# 03-Display.net
KiCad netlist of a schematic drawn in Altium Designer
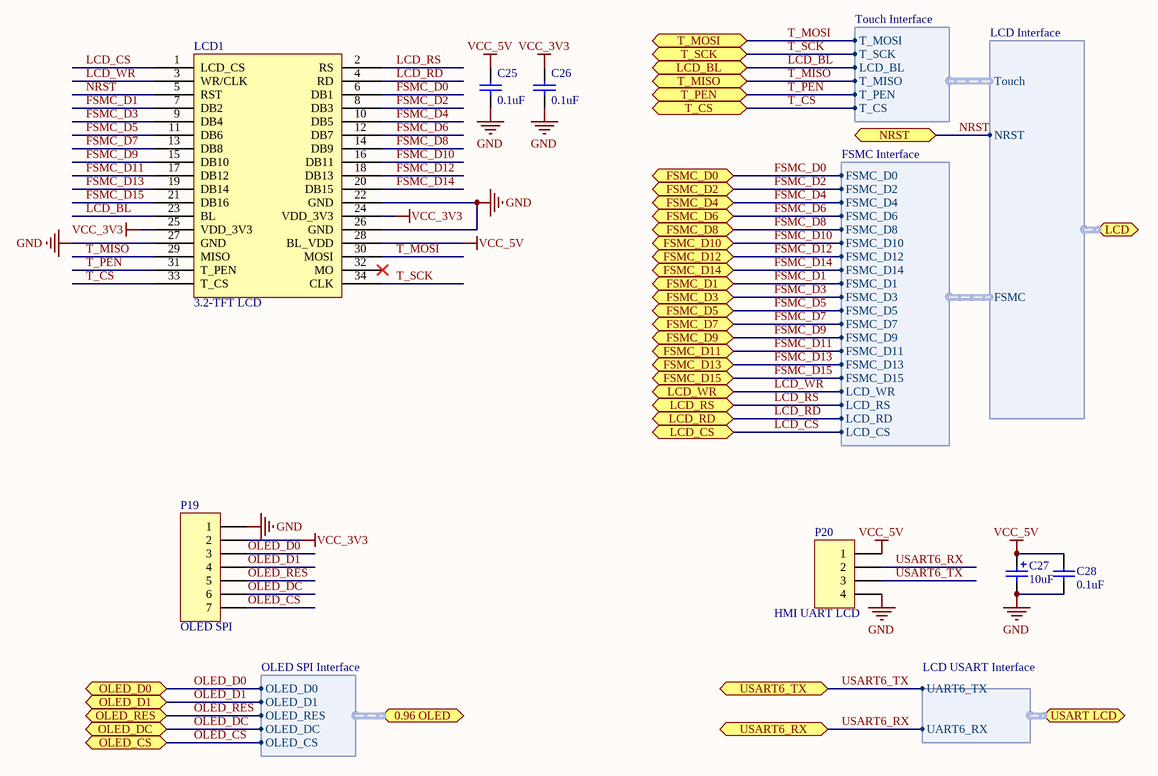
[diagram p0: 03-Display.SchDoc]

(export (version "E")
  (design (tool "Eeschema 10.0.6"))
  (components
    (comp (ref "C25")
      (value "0.1uF")
      (footprint "0603C")
      (description "CAP CER 10000PF 100V X7R 0603")
      (fields
        (field (name "MANUFACTURER") "TDK Corporation")
        (field (name "MANUFACTURER PART NUMBER") "C1608X7R2A103K080AA")
      )
      (libsource (lib "Desiger_Schlib") (part "Cap1"))
    )
    (comp (ref "C26")
      (value "0.1uF")
      (footprint "0603C")
      (description "CAP CER 10000PF 100V X7R 0603")
      (fields
        (field (name "MANUFACTURER") "TDK Corporation")
        (field (name "MANUFACTURER PART NUMBER") "C1608X7R2A103K080AA")
      )
      (libsource (lib "Desiger_Schlib") (part "Cap1"))
    )
    (comp (ref "C27")
      (value "10uF")
      (footprint "1206T")
      (description "CAP TANT 10UF 10V 10% 1206")
      (fields
        (field (name "MANUFACTURER") "KEMET")
        (field (name "MANUFACTURER PART NUMBER") "T491A106K010AT7280")
      )
      (libsource (lib "Desiger_Schlib") (part "Cap2"))
    )
    (comp (ref "C28")
      (value "0.1uF")
      (footprint "0603C")
      (description "CAP CER 10000PF 100V X7R 0603")
      (fields
        (field (name "MANUFACTURER") "TDK Corporation")
        (field (name "MANUFACTURER PART NUMBER") "C1608X7R2A103K080AA")
      )
      (libsource (lib "Desiger_Schlib") (part "Cap1"))
    )
    (comp (ref "LCD1")
      (value "3.2-TFT LCD")
      (footprint "3.2_LCD")
      (libsource (lib "SCH-LIB") (part "3.2-TFT LCD"))
    )
    (comp (ref "P19")
      (value "OLED SPI")
      (footprint "OLED_0.96_SPI")
      (description "Header, 7-Pin")
      (fields (field (name "PUBLISHER") "Altium Limited"))
      (libsource (lib "Miscellaneous Connectors") (part "Header 7"))
    )
    (comp (ref "P20")
      (value "HMI UART LCD")
      (footprint "xh_4")
      (description "Header, 4-Pin")
      (fields (field (name "PUBLISHER") "Altium Limited"))
      (libsource (lib "Miscellaneous Connectors") (part "Header 4"))
    )
  )
  (nets
    (net (code "8") (name "/FSMC_D0") (class "Default")
      (node (ref "LCD1") (pin "6") (pinfunction "DB1_6") (pintype "passive"))
    )
    (net (code "9") (name "/FSMC_D1") (class "Default")
      (node (ref "LCD1") (pin "7") (pinfunction "DB2_7") (pintype "passive"))
    )
    (net (code "10") (name "/FSMC_D2") (class "Default")
      (node (ref "LCD1") (pin "8") (pinfunction "DB3_8") (pintype "passive"))
    )
    (net (code "11") (name "/FSMC_D3") (class "Default")
      (node (ref "LCD1") (pin "9") (pinfunction "DB4_9") (pintype "passive"))
    )
    (net (code "12") (name "/FSMC_D4") (class "Default")
      (node (ref "LCD1") (pin "10") (pinfunction "DB5_10") (pintype "passive"))
    )
    (net (code "13") (name "/FSMC_D5") (class "Default")
      (node (ref "LCD1") (pin "11") (pinfunction "DB6_11") (pintype "passive"))
    )
    (net (code "14") (name "/FSMC_D6") (class "Default")
      (node (ref "LCD1") (pin "12") (pinfunction "DB7_12") (pintype "passive"))
    )
    (net (code "15") (name "/FSMC_D7") (class "Default")
      (node (ref "LCD1") (pin "13") (pinfunction "DB8_13") (pintype "passive"))
    )
    (net (code "16") (name "/FSMC_D8") (class "Default")
      (node (ref "LCD1") (pin "14") (pinfunction "DB9_14") (pintype "passive"))
    )
    (net (code "17") (name "/FSMC_D9") (class "Default")
      (node (ref "LCD1") (pin "15") (pinfunction "DB10_15") (pintype "passive"))
    )
    (net (code "18") (name "/FSMC_D10") (class "Default")
      (node (ref "LCD1") (pin "16") (pinfunction "DB11_16") (pintype "passive"))
    )
    (net (code "19") (name "/FSMC_D11") (class "Default")
      (node (ref "LCD1") (pin "17") (pinfunction "DB12_17") (pintype "passive"))
    )
    (net (code "20") (name "/FSMC_D12") (class "Default")
      (node (ref "LCD1") (pin "18") (pinfunction "DB13_18") (pintype "passive"))
    )
    (net (code "21") (name "/FSMC_D13") (class "Default")
      (node (ref "LCD1") (pin "19") (pinfunction "DB14_19") (pintype "passive"))
    )
    (net (code "22") (name "/FSMC_D14") (class "Default")
      (node (ref "LCD1") (pin "20") (pinfunction "DB15_20") (pintype "passive"))
    )
    (net (code "23") (name "/FSMC_D15") (class "Default")
      (node (ref "LCD1") (pin "21") (pinfunction "DB16_21") (pintype "passive"))
    )
    (net (code "24") (name "/LCD_BL") (class "Default")
      (node (ref "LCD1") (pin "23") (pinfunction "BL_23") (pintype "passive"))
    )
    (net (code "25") (name "/LCD_CS") (class "Default")
      (node (ref "LCD1") (pin "1") (pinfunction "LCD_CS_1") (pintype "passive"))
    )
    (net (code "26") (name "/LCD_RD") (class "Default")
      (node (ref "LCD1") (pin "4") (pinfunction "RD_4") (pintype "passive"))
    )
    (net (code "27") (name "/LCD_RS") (class "Default")
      (node (ref "LCD1") (pin "2") (pinfunction "RS_2") (pintype "passive"))
    )
    (net (code "28") (name "/LCD_WR") (class "Default")
      (node (ref "LCD1") (pin "3") (pinfunction "WR/CLK_3") (pintype "passive"))
    )
    (net (code "29") (name "/NRST") (class "Default")
      (node (ref "LCD1") (pin "5") (pinfunction "RST_5") (pintype "passive"))
    )
    (net (code "30") (name "/OLED_CS") (class "Default")
      (node (ref "P19") (pin "7") (pinfunction "7_7") (pintype "passive"))
    )
    (net (code "31") (name "/OLED_D0") (class "Default")
      (node (ref "P19") (pin "3") (pinfunction "3_3") (pintype "passive"))
    )
    (net (code "32") (name "/OLED_D1") (class "Default")
      (node (ref "P19") (pin "4") (pinfunction "4_4") (pintype "passive"))
    )
    (net (code "33") (name "/OLED_DC") (class "Default")
      (node (ref "P19") (pin "6") (pinfunction "6_6") (pintype "passive"))
    )
    (net (code "34") (name "/OLED_RES") (class "Default")
      (node (ref "P19") (pin "5") (pinfunction "5_5") (pintype "passive"))
    )
    (net (code "35") (name "/T_CS") (class "Default")
      (node (ref "LCD1") (pin "33") (pinfunction "T_CS_33") (pintype "passive"))
    )
    (net (code "36") (name "/T_MISO") (class "Default")
      (node (ref "LCD1") (pin "29") (pinfunction "MISO_29") (pintype "passive"))
    )
    (net (code "37") (name "/T_MOSI") (class "Default")
      (node (ref "LCD1") (pin "30") (pinfunction "MOSI_30") (pintype "passive"))
    )
    (net (code "38") (name "/T_PEN") (class "Default")
      (node (ref "LCD1") (pin "31") (pinfunction "T_PEN_31") (pintype "passive"))
    )
    (net (code "39") (name "/T_SCK") (class "Default")
      (node (ref "LCD1") (pin "34") (pinfunction "CLK_34") (pintype "passive"))
    )
    (net (code "40") (name "/USART6_RX") (class "Default")
      (node (ref "P20") (pin "2") (pinfunction "2_2") (pintype "passive"))
    )
    (net (code "41") (name "/USART6_TX") (class "Default")
      (node (ref "P20") (pin "3") (pinfunction "3_3") (pintype "passive"))
    )
    (net (code "47") (name "GND") (class "Default")
      (node (ref "C25") (pin "2") (pinfunction "2_2") (pintype "passive"))
      (node (ref "C26") (pin "2") (pinfunction "2_2") (pintype "passive"))
      (node (ref "C27") (pin "2") (pinfunction "-_2") (pintype "passive"))
      (node (ref "C28") (pin "1") (pinfunction "1_1") (pintype "passive"))
      (node (ref "LCD1") (pin "22") (pinfunction "GND_22") (pintype "passive"))
      (node (ref "LCD1") (pin "26") (pinfunction "GND_26") (pintype "passive"))
      (node (ref "LCD1") (pin "27") (pinfunction "GND_27") (pintype "passive"))
      (node (ref "P19") (pin "1") (pinfunction "1_1") (pintype "passive"))
      (node (ref "P20") (pin "4") (pinfunction "4_4") (pintype "passive"))
    )
    (net (code "48") (name "VCC_3V3") (class "Default")
      (node (ref "C26") (pin "1") (pinfunction "1_1") (pintype "passive"))
      (node (ref "LCD1") (pin "24") (pinfunction "VDD_3V3_24") (pintype "passive"))
      (node (ref "LCD1") (pin "25") (pinfunction "VDD_3V3_25") (pintype "passive"))
      (node (ref "P19") (pin "2") (pinfunction "2_2") (pintype "passive"))
    )
    (net (code "49") (name "VCC_5V") (class "Default")
      (node (ref "C25") (pin "1") (pinfunction "1_1") (pintype "passive"))
      (node (ref "C27") (pin "1") (pinfunction "+_1") (pintype "passive"))
      (node (ref "C28") (pin "2") (pinfunction "2_2") (pintype "passive"))
      (node (ref "LCD1") (pin "28") (pinfunction "BL_VDD_28") (pintype "passive"))
      (node (ref "P20") (pin "1") (pinfunction "1_1") (pintype "passive"))
    )
    (net (code "50") (name "unconnected-(LCD1-MO-Pad32)") (class "Default")
      (node (ref "LCD1") (pin "32") (pinfunction "MO_32") (pintype "passive+no_connect"))
    )
  )
)
